# LightShaker-3.net
KiCad netlist of a schematic drawn in EAGLE
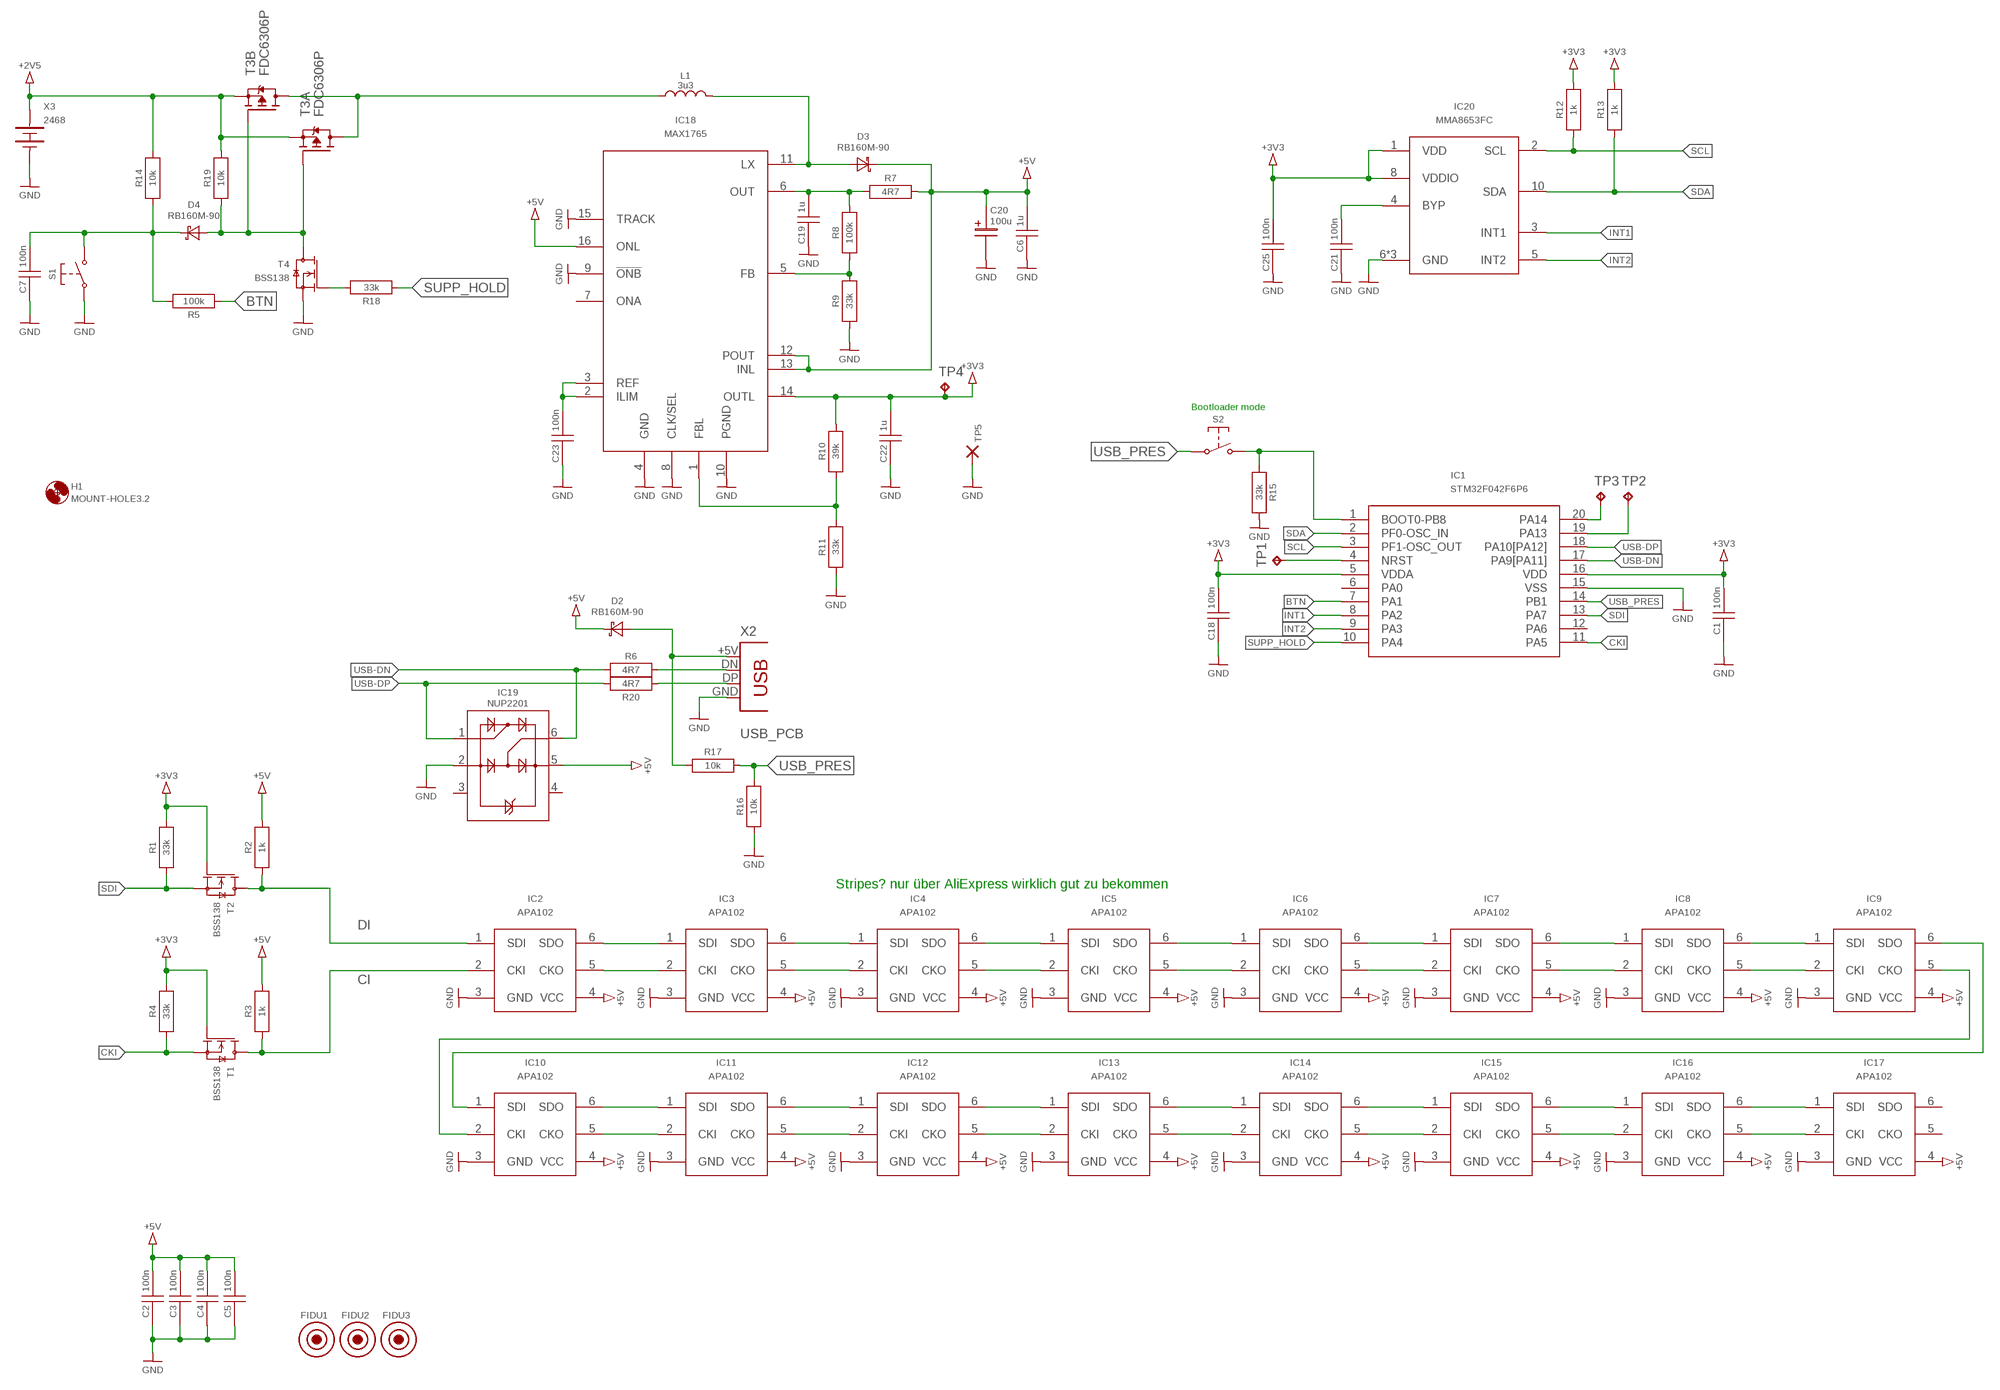
[diagram p0: schematic, sheet 1]

(export (version "E")
  (design (tool "Eeschema 10.0.6"))
  (components
    (comp (ref "C1")
      (value "100n")
      (footprint "eagle-import:SM_1206")
      (fields (field (name "MECHPART") "FALSE") (field (name "PARTNR") "E0001400"))
      (libsource (lib "eagle-import") (part "C1206"))
    )
    (comp (ref "C2")
      (value "100n")
      (footprint "eagle-import:SM_1206")
      (fields (field (name "MECHPART") "FALSE") (field (name "PARTNR") "E0001400"))
      (libsource (lib "eagle-import") (part "C1206"))
    )
    (comp (ref "C3")
      (value "100n")
      (footprint "eagle-import:SM_1206")
      (fields (field (name "MECHPART") "FALSE") (field (name "PARTNR") "E0001400"))
      (libsource (lib "eagle-import") (part "C1206"))
    )
    (comp (ref "C4")
      (value "100n")
      (footprint "eagle-import:SM_1206")
      (fields (field (name "MECHPART") "FALSE") (field (name "PARTNR") "E0001400"))
      (libsource (lib "eagle-import") (part "C1206"))
    )
    (comp (ref "C5")
      (value "100n")
      (footprint "eagle-import:SM_1206")
      (fields (field (name "MECHPART") "FALSE") (field (name "PARTNR") "E0001400"))
      (libsource (lib "eagle-import") (part "C1206"))
    )
    (comp (ref "C6")
      (value "1u")
      (footprint "eagle-import:SM_1206")
      (fields (field (name "MECHPART") "FALSE") (field (name "PARTNR") "E0487200"))
      (libsource (lib "eagle-import") (part "C1206"))
    )
    (comp (ref "C7")
      (value "100n")
      (footprint "eagle-import:SM_1206")
      (fields (field (name "MECHPART") "FALSE") (field (name "PARTNR") "E0001400"))
      (libsource (lib "eagle-import") (part "C1206"))
    )
    (comp (ref "C18")
      (value "100n")
      (footprint "eagle-import:SM_1206")
      (fields (field (name "MECHPART") "FALSE") (field (name "PARTNR") "E0001400"))
      (libsource (lib "eagle-import") (part "C1206"))
    )
    (comp (ref "C19")
      (value "1u")
      (footprint "eagle-import:SM_1206")
      (fields (field (name "MECHPART") "FALSE") (field (name "PARTNR") "E0487200"))
      (libsource (lib "eagle-import") (part "C1206"))
    )
    (comp (ref "C20")
      (value "100u")
      (footprint "eagle-import:SM_SIZE-D")
      (fields (field (name "MECHPART") "FALSE") (field (name "PARTNR") "E0242200"))
      (libsource (lib "eagle-import") (part "CPOLSIZE-D"))
    )
    (comp (ref "C21")
      (value "100n")
      (footprint "eagle-import:SM_1206")
      (fields (field (name "MECHPART") "FALSE") (field (name "PARTNR") "E0001400"))
      (libsource (lib "eagle-import") (part "C1206"))
    )
    (comp (ref "C22")
      (value "1u")
      (footprint "eagle-import:SM_1206")
      (fields (field (name "MECHPART") "FALSE") (field (name "PARTNR") "E0487200"))
      (libsource (lib "eagle-import") (part "C1206"))
    )
    (comp (ref "C23")
      (value "100n")
      (footprint "eagle-import:SM_1206")
      (fields (field (name "MECHPART") "FALSE") (field (name "PARTNR") "E0001400"))
      (libsource (lib "eagle-import") (part "C1206"))
    )
    (comp (ref "C25")
      (value "100n")
      (footprint "eagle-import:SM_1206")
      (fields (field (name "MECHPART") "FALSE") (field (name "PARTNR") "E0001400"))
      (libsource (lib "eagle-import") (part "C1206"))
    )
    (comp (ref "D2")
      (value "RB160M-90")
      (footprint "eagle-import:SM_SOD123_POL")
      (libsource (lib "eagle-import") (part "RB160M-90"))
    )
    (comp (ref "D3")
      (value "RB160M-90")
      (footprint "eagle-import:SM_SOD123_POL")
      (libsource (lib "eagle-import") (part "RB160M-90"))
    )
    (comp (ref "D4")
      (value "RB160M-90")
      (footprint "eagle-import:SM_SOD123_POL")
      (libsource (lib "eagle-import") (part "RB160M-90"))
    )
    (comp (ref "FIDU1")
      (value "FIDU_ROUND_NEW")
      (footprint "eagle-import:FIDUCIAL_LOETSTOPP")
      (libsource (lib "eagle-import") (part "FIDU_ROUND_NEW"))
    )
    (comp (ref "FIDU2")
      (value "FIDU_ROUND_NEW")
      (footprint "eagle-import:FIDUCIAL_LOETSTOPP")
      (libsource (lib "eagle-import") (part "FIDU_ROUND_NEW"))
    )
    (comp (ref "FIDU3")
      (value "FIDU_ROUND_NEW")
      (footprint "eagle-import:FIDUCIAL_LOETSTOPP")
      (libsource (lib "eagle-import") (part "FIDU_ROUND_NEW"))
    )
    (comp (ref "H1")
      (value "MOUNT-HOLE3.2")
      (footprint "eagle-import:3.2")
      (libsource (lib "eagle-import") (part "MOUNT-HOLE3.2"))
    )
    (comp (ref "IC1")
      (value "STM32F042F6P6")
      (footprint "eagle-import:SM_TSSOP20")
      (libsource (lib "eagle-import") (part "STM32F042F6P6"))
    )
    (comp (ref "IC2")
      (value "APA102")
      (footprint "eagle-import:SM_LED_PLCC6")
      (libsource (lib "eagle-import") (part "APA102"))
    )
    (comp (ref "IC3")
      (value "APA102")
      (footprint "eagle-import:SM_LED_PLCC6")
      (libsource (lib "eagle-import") (part "APA102"))
    )
    (comp (ref "IC4")
      (value "APA102")
      (footprint "eagle-import:SM_LED_PLCC6")
      (libsource (lib "eagle-import") (part "APA102"))
    )
    (comp (ref "IC5")
      (value "APA102")
      (footprint "eagle-import:SM_LED_PLCC6")
      (libsource (lib "eagle-import") (part "APA102"))
    )
    (comp (ref "IC6")
      (value "APA102")
      (footprint "eagle-import:SM_LED_PLCC6")
      (libsource (lib "eagle-import") (part "APA102"))
    )
    (comp (ref "IC7")
      (value "APA102")
      (footprint "eagle-import:SM_LED_PLCC6")
      (libsource (lib "eagle-import") (part "APA102"))
    )
    (comp (ref "IC8")
      (value "APA102")
      (footprint "eagle-import:SM_LED_PLCC6")
      (libsource (lib "eagle-import") (part "APA102"))
    )
    (comp (ref "IC9")
      (value "APA102")
      (footprint "eagle-import:SM_LED_PLCC6")
      (libsource (lib "eagle-import") (part "APA102"))
    )
    (comp (ref "IC10")
      (value "APA102")
      (footprint "eagle-import:SM_LED_PLCC6")
      (libsource (lib "eagle-import") (part "APA102"))
    )
    (comp (ref "IC11")
      (value "APA102")
      (footprint "eagle-import:SM_LED_PLCC6")
      (libsource (lib "eagle-import") (part "APA102"))
    )
    (comp (ref "IC12")
      (value "APA102")
      (footprint "eagle-import:SM_LED_PLCC6")
      (libsource (lib "eagle-import") (part "APA102"))
    )
    (comp (ref "IC13")
      (value "APA102")
      (footprint "eagle-import:SM_LED_PLCC6")
      (libsource (lib "eagle-import") (part "APA102"))
    )
    (comp (ref "IC14")
      (value "APA102")
      (footprint "eagle-import:SM_LED_PLCC6")
      (libsource (lib "eagle-import") (part "APA102"))
    )
    (comp (ref "IC15")
      (value "APA102")
      (footprint "eagle-import:SM_LED_PLCC6")
      (libsource (lib "eagle-import") (part "APA102"))
    )
    (comp (ref "IC16")
      (value "APA102")
      (footprint "eagle-import:SM_LED_PLCC6")
      (libsource (lib "eagle-import") (part "APA102"))
    )
    (comp (ref "IC17")
      (value "APA102")
      (footprint "eagle-import:SM_LED_PLCC6")
      (libsource (lib "eagle-import") (part "APA102"))
    )
    (comp (ref "IC18")
      (value "MAX1765")
      (footprint "eagle-import:SM_QSOP16")
      (libsource (lib "eagle-import") (part "MAX1765"))
    )
    (comp (ref "IC19")
      (value "NUP2201")
      (footprint "eagle-import:TSOP6")
      (libsource (lib "eagle-import") (part "NUP2201"))
    )
    (comp (ref "IC20")
      (value "MMA8653FC")
      (footprint "eagle-import:SM_DFN10")
      (libsource (lib "eagle-import") (part "MMA8653FC"))
    )
    (comp (ref "L1")
      (value "3u3")
      (footprint "eagle-import:SM_L_MOS6020")
      (libsource (lib "eagle-import") (part "L_MOS6020"))
    )
    (comp (ref "R1")
      (value "33k")
      (footprint "eagle-import:SM_1206")
      (fields (field (name "MECHPART") "FALSE") (field (name "PARTNR") "E0149800"))
      (libsource (lib "eagle-import") (part "R1206"))
    )
    (comp (ref "R2")
      (value "1k")
      (footprint "eagle-import:SM_1206")
      (fields (field (name "MECHPART") "FALSE") (field (name "PARTNR") "E0002500"))
      (libsource (lib "eagle-import") (part "R1206"))
    )
    (comp (ref "R3")
      (value "1k")
      (footprint "eagle-import:SM_1206")
      (fields (field (name "MECHPART") "FALSE") (field (name "PARTNR") "E0002500"))
      (libsource (lib "eagle-import") (part "R1206"))
    )
    (comp (ref "R4")
      (value "33k")
      (footprint "eagle-import:SM_1206")
      (fields (field (name "MECHPART") "FALSE") (field (name "PARTNR") "E0149800"))
      (libsource (lib "eagle-import") (part "R1206"))
    )
    (comp (ref "R5")
      (value "100k")
      (footprint "eagle-import:SM_1206")
      (fields (field (name "MECHPART") "FALSE"))
      (libsource (lib "eagle-import") (part "R1206"))
    )
    (comp (ref "R6")
      (value "4R7")
      (footprint "eagle-import:SM_1206")
      (fields (field (name "MECHPART") "FALSE"))
      (libsource (lib "eagle-import") (part "R1206"))
    )
    (comp (ref "R7")
      (value "4R7")
      (footprint "eagle-import:SM_1206")
      (fields (field (name "MECHPART") "FALSE") (field (name "PARTNR") "E0821300"))
      (libsource (lib "eagle-import") (part "R1206"))
    )
    (comp (ref "R8")
      (value "100k")
      (footprint "eagle-import:SM_1206")
      (fields (field (name "MECHPART") "FALSE") (field (name "PARTNR") "E0002800"))
      (libsource (lib "eagle-import") (part "R1206"))
    )
    (comp (ref "R9")
      (value "33k")
      (footprint "eagle-import:SM_1206")
      (fields (field (name "MECHPART") "FALSE") (field (name "PARTNR") "E0149800"))
      (libsource (lib "eagle-import") (part "R1206"))
    )
    (comp (ref "R10")
      (value "39k")
      (footprint "eagle-import:SM_1206")
      (fields (field (name "MECHPART") "FALSE"))
      (libsource (lib "eagle-import") (part "R1206"))
    )
    (comp (ref "R11")
      (value "33k")
      (footprint "eagle-import:SM_1206")
      (fields (field (name "MECHPART") "FALSE") (field (name "PARTNR") "E0149800"))
      (libsource (lib "eagle-import") (part "R1206"))
    )
    (comp (ref "R12")
      (value "1k")
      (footprint "eagle-import:SM_1206")
      (fields (field (name "MECHPART") "FALSE") (field (name "PARTNR") "E0002500"))
      (libsource (lib "eagle-import") (part "R1206"))
    )
    (comp (ref "R13")
      (value "1k")
      (footprint "eagle-import:SM_1206")
      (fields (field (name "MECHPART") "FALSE") (field (name "PARTNR") "E0002500"))
      (libsource (lib "eagle-import") (part "R1206"))
    )
    (comp (ref "R14")
      (value "10k")
      (footprint "eagle-import:SM_1206")
      (fields (field (name "MECHPART") "FALSE") (field (name "PARTNR") "E0002700"))
      (libsource (lib "eagle-import") (part "R1206"))
    )
    (comp (ref "R15")
      (value "33k")
      (footprint "eagle-import:SM_1206")
      (fields (field (name "MECHPART") "FALSE") (field (name "PARTNR") "E0149800"))
      (libsource (lib "eagle-import") (part "R1206"))
    )
    (comp (ref "R16")
      (value "10k")
      (footprint "eagle-import:SM_1206")
      (fields (field (name "MECHPART") "FALSE") (field (name "PARTNR") "E0002700"))
      (libsource (lib "eagle-import") (part "R1206"))
    )
    (comp (ref "R17")
      (value "10k")
      (footprint "eagle-import:SM_1206")
      (fields (field (name "MECHPART") "FALSE") (field (name "PARTNR") "E0002700"))
      (libsource (lib "eagle-import") (part "R1206"))
    )
    (comp (ref "R18")
      (value "33k")
      (footprint "eagle-import:SM_1206")
      (fields (field (name "MECHPART") "FALSE") (field (name "PARTNR") "E0149800"))
      (libsource (lib "eagle-import") (part "R1206"))
    )
    (comp (ref "R19")
      (value "10k")
      (footprint "eagle-import:SM_1206")
      (fields (field (name "MECHPART") "FALSE") (field (name "PARTNR") "E0002800"))
      (libsource (lib "eagle-import") (part "R1206"))
    )
    (comp (ref "R20")
      (value "4R7")
      (footprint "eagle-import:SM_1206")
      (fields (field (name "MECHPART") "FALSE"))
      (libsource (lib "eagle-import") (part "R1206"))
    )
    (comp (ref "S1")
      (value "PUSH-BUTTON_SMD")
      (footprint "eagle-import:PUSH-BUTTON_SMD")
      (libsource (lib "eagle-import") (part "PUSH-BUTTON_SMD"))
    )
    (comp (ref "S2")
      (value "PUSH-BUTTON_SMD")
      (footprint "eagle-import:PUSH-BUTTON_SMD")
      (libsource (lib "eagle-import") (part "PUSH-BUTTON_SMD"))
    )
    (comp (ref "T1")
      (value "BSS138")
      (footprint "eagle-import:SM_SOT23")
      (libsource (lib "eagle-import") (part "BSS138"))
    )
    (comp (ref "T2")
      (value "BSS138")
      (footprint "eagle-import:SM_SOT23")
      (libsource (lib "eagle-import") (part "BSS138"))
    )
    (comp (ref "T3")
      (value "FDC6306P")
      (footprint "eagle-import:TSOP6")
      (fields (field (name "PARTNR") "E0662100"))
      (libsource (lib "eagle-import") (part "FDC6306P"))
    )
    (comp (ref "T4")
      (value "BSS138")
      (footprint "eagle-import:SM_SOT23")
      (libsource (lib "eagle-import") (part "BSS138"))
    )
    (comp (ref "TP1")
      (value "TPTP12R")
      (footprint "eagle-import:TP12R")
      (libsource (lib "eagle-import") (part "TPTP12R"))
    )
    (comp (ref "TP2")
      (value "TPTP12R")
      (footprint "eagle-import:TP12R")
      (libsource (lib "eagle-import") (part "TPTP12R"))
    )
    (comp (ref "TP3")
      (value "TPTP12R")
      (footprint "eagle-import:TP12R")
      (libsource (lib "eagle-import") (part "TPTP12R"))
    )
    (comp (ref "TP4")
      (value "TPTP12R")
      (footprint "eagle-import:TP12R")
      (libsource (lib "eagle-import") (part "TPTP12R"))
    )
    (comp (ref "TP5")
      (value "CHECKER_1206")
      (footprint "eagle-import:SM_RCW_1206")
      (libsource (lib "eagle-import") (part "CHECKER_1206"))
    )
    (comp (ref "X2")
      (value "USB_PCB")
      (footprint "eagle-import:USB_PCB")
      (libsource (lib "eagle-import") (part "USB_PCB"))
    )
    (comp (ref "X3")
      (value "2468")
      (footprint "eagle-import:2468")
      (libsource (lib "eagle-import") (part "2468"))
    )
  )
  (nets
    (net (code "1") (name "+2V5") (class "Default")
      (node (ref "R14") (pin "2") (pinfunction "2_2") (pintype "bidirectional"))
      (node (ref "R19") (pin "2") (pinfunction "2_2") (pintype "bidirectional"))
      (node (ref "T3") (pin "2") (pinfunction "S_2") (pintype "passive"))
      (node (ref "T3") (pin "5") (pinfunction "S_5") (pintype "passive"))
      (node (ref "X3") (pin "POS") (pinfunction "POS_POS") (pintype "bidirectional"))
    )
    (net (code "2") (name "+3V3") (class "Default")
      (node (ref "C1") (pin "2") (pinfunction "2_2") (pintype "bidirectional"))
      (node (ref "C18") (pin "2") (pinfunction "2_2") (pintype "bidirectional"))
      (node (ref "C22") (pin "2") (pinfunction "2_2") (pintype "bidirectional"))
      (node (ref "C25") (pin "2") (pinfunction "2_2") (pintype "bidirectional"))
      (node (ref "IC1") (pin "16") (pinfunction "VDD_16") (pintype "bidirectional"))
      (node (ref "IC1") (pin "5") (pinfunction "VDDA_5") (pintype "bidirectional"))
      (node (ref "IC18") (pin "14") (pinfunction "OUTL_14") (pintype "bidirectional"))
      (node (ref "IC20") (pin "1") (pinfunction "VDD_1") (pintype "bidirectional"))
      (node (ref "IC20") (pin "8") (pinfunction "VDDIO_8") (pintype "bidirectional"))
      (node (ref "R1") (pin "2") (pinfunction "2_2") (pintype "bidirectional"))
      (node (ref "R10") (pin "2") (pinfunction "2_2") (pintype "bidirectional"))
      (node (ref "R12") (pin "2") (pinfunction "2_2") (pintype "bidirectional"))
      (node (ref "R13") (pin "2") (pinfunction "2_2") (pintype "bidirectional"))
      (node (ref "R4") (pin "2") (pinfunction "2_2") (pintype "bidirectional"))
      (node (ref "T1") (pin "1") (pinfunction "G_1") (pintype "bidirectional"))
      (node (ref "T2") (pin "1") (pinfunction "G_1") (pintype "bidirectional"))
      (node (ref "TP4") (pin "TP") (pinfunction "TP_TP") (pintype "input"))
    )
    (net (code "3") (name "+5V") (class "Default")
      (node (ref "C2") (pin "2") (pinfunction "2_2") (pintype "bidirectional"))
      (node (ref "C20") (pin "POS") (pinfunction "POS_POS") (pintype "bidirectional"))
      (node (ref "C3") (pin "2") (pinfunction "2_2") (pintype "bidirectional"))
      (node (ref "C4") (pin "2") (pinfunction "2_2") (pintype "bidirectional"))
      (node (ref "C5") (pin "2") (pinfunction "2_2") (pintype "bidirectional"))
      (node (ref "C6") (pin "2") (pinfunction "2_2") (pintype "bidirectional"))
      (node (ref "D2") (pin "C") (pinfunction "C_C") (pintype "bidirectional"))
      (node (ref "D3") (pin "C") (pinfunction "C_C") (pintype "bidirectional"))
      (node (ref "IC10") (pin "4") (pinfunction "VCC_4") (pintype "bidirectional"))
      (node (ref "IC11") (pin "4") (pinfunction "VCC_4") (pintype "bidirectional"))
      (node (ref "IC12") (pin "4") (pinfunction "VCC_4") (pintype "bidirectional"))
      (node (ref "IC13") (pin "4") (pinfunction "VCC_4") (pintype "bidirectional"))
      (node (ref "IC14") (pin "4") (pinfunction "VCC_4") (pintype "bidirectional"))
      (node (ref "IC15") (pin "4") (pinfunction "VCC_4") (pintype "bidirectional"))
      (node (ref "IC16") (pin "4") (pinfunction "VCC_4") (pintype "bidirectional"))
      (node (ref "IC17") (pin "4") (pinfunction "VCC_4") (pintype "bidirectional"))
      (node (ref "IC18") (pin "12") (pinfunction "POUT_12") (pintype "bidirectional"))
      (node (ref "IC18") (pin "13") (pinfunction "INL_13") (pintype "bidirectional"))
      (node (ref "IC18") (pin "16") (pinfunction "ONL_16") (pintype "bidirectional"))
      (node (ref "IC19") (pin "5") (pinfunction "VP_5") (pintype "bidirectional"))
      (node (ref "IC2") (pin "4") (pinfunction "VCC_4") (pintype "bidirectional"))
      (node (ref "IC3") (pin "4") (pinfunction "VCC_4") (pintype "bidirectional"))
      (node (ref "IC4") (pin "4") (pinfunction "VCC_4") (pintype "bidirectional"))
      (node (ref "IC5") (pin "4") (pinfunction "VCC_4") (pintype "bidirectional"))
      (node (ref "IC6") (pin "4") (pinfunction "VCC_4") (pintype "bidirectional"))
      (node (ref "IC7") (pin "4") (pinfunction "VCC_4") (pintype "bidirectional"))
      (node (ref "IC8") (pin "4") (pinfunction "VCC_4") (pintype "bidirectional"))
      (node (ref "IC9") (pin "4") (pinfunction "VCC_4") (pintype "bidirectional"))
      (node (ref "R2") (pin "2") (pinfunction "2_2") (pintype "bidirectional"))
      (node (ref "R3") (pin "2") (pinfunction "2_2") (pintype "bidirectional"))
      (node (ref "R7") (pin "2") (pinfunction "2_2") (pintype "bidirectional"))
    )
    (net (code "4") (name "/CI") (class "Default")
      (node (ref "IC2") (pin "2") (pinfunction "CKI_2") (pintype "bidirectional"))
      (node (ref "R3") (pin "1") (pinfunction "1_1") (pintype "bidirectional"))
      (node (ref "T1") (pin "3") (pinfunction "D_3") (pintype "bidirectional"))
    )
    (net (code "5") (name "/DI") (class "Default")
      (node (ref "IC2") (pin "1") (pinfunction "SDI_1") (pintype "bidirectional"))
      (node (ref "R2") (pin "1") (pinfunction "1_1") (pintype "bidirectional"))
      (node (ref "T2") (pin "3") (pinfunction "D_3") (pintype "bidirectional"))
    )
    (net (code "6") (name "BTN") (class "Default")
      (node (ref "IC1") (pin "7") (pinfunction "PA1_7") (pintype "bidirectional"))
      (node (ref "R5") (pin "1") (pinfunction "1_1") (pintype "bidirectional"))
    )
    (net (code "7") (name "CKI") (class "Default")
      (node (ref "IC1") (pin "11") (pinfunction "PA5_11") (pintype "bidirectional"))
      (node (ref "R4") (pin "1") (pinfunction "1_1") (pintype "bidirectional"))
      (node (ref "T1") (pin "2") (pinfunction "S_2") (pintype "bidirectional"))
    )
    (net (code "8") (name "GND") (class "Default")
      (node (ref "C1") (pin "1") (pinfunction "1_1") (pintype "bidirectional"))
      (node (ref "C18") (pin "1") (pinfunction "1_1") (pintype "bidirectional"))
      (node (ref "C19") (pin "1") (pinfunction "1_1") (pintype "bidirectional"))
      (node (ref "C2") (pin "1") (pinfunction "1_1") (pintype "bidirectional"))
      (node (ref "C20") (pin "NEG") (pinfunction "NEG_NEG") (pintype "bidirectional"))
      (node (ref "C21") (pin "1") (pinfunction "1_1") (pintype "bidirectional"))
      (node (ref "C22") (pin "1") (pinfunction "1_1") (pintype "bidirectional"))
      (node (ref "C23") (pin "1") (pinfunction "1_1") (pintype "bidirectional"))
      (node (ref "C25") (pin "1") (pinfunction "1_1") (pintype "bidirectional"))
      (node (ref "C3") (pin "1") (pinfunction "1_1") (pintype "bidirectional"))
      (node (ref "C4") (pin "1") (pinfunction "1_1") (pintype "bidirectional"))
      (node (ref "C5") (pin "1") (pinfunction "1_1") (pintype "bidirectional"))
      (node (ref "C6") (pin "1") (pinfunction "1_1") (pintype "bidirectional"))
      (node (ref "C7") (pin "1") (pinfunction "1_1") (pintype "bidirectional"))
      (node (ref "IC1") (pin "15") (pinfunction "VSS_15") (pintype "bidirectional"))
      (node (ref "IC10") (pin "3") (pinfunction "GND_3") (pintype "bidirectional"))
      (node (ref "IC11") (pin "3") (pinfunction "GND_3") (pintype "bidirectional"))
      (node (ref "IC12") (pin "3") (pinfunction "GND_3") (pintype "bidirectional"))
      (node (ref "IC13") (pin "3") (pinfunction "GND_3") (pintype "bidirectional"))
      (node (ref "IC14") (pin "3") (pinfunction "GND_3") (pintype "bidirectional"))
      (node (ref "IC15") (pin "3") (pinfunction "GND_3") (pintype "bidirectional"))
      (node (ref "IC16") (pin "3") (pinfunction "GND_3") (pintype "bidirectional"))
      (node (ref "IC17") (pin "3") (pinfunction "GND_3") (pintype "bidirectional"))
      (node (ref "IC18") (pin "10") (pinfunction "PGND_10") (pintype "bidirectional"))
      (node (ref "IC18") (pin "15") (pinfunction "TRACK_15") (pintype "bidirectional"))
      (node (ref "IC18") (pin "4") (pinfunction "GND_4") (pintype "bidirectional"))
      (node (ref "IC18") (pin "8") (pinfunction "CLK/SEL_8") (pintype "bidirectional"))
      (node (ref "IC18") (pin "9") (pinfunction "~{ONB}_9") (pintype "bidirectional"))
      (node (ref "IC19") (pin "2") (pinfunction "GND_2") (pintype "bidirectional"))
      (node (ref "IC2") (pin "3") (pinfunction "GND_3") (pintype "bidirectional"))
      (node (ref "IC20") (pin "6") (pinfunction "GND_6") (pintype "bidirectional"))
      (node (ref "IC20") (pin "7") (pinfunction "GND_7") (pintype "bidirectional"))
      (node (ref "IC20") (pin "9") (pinfunction "GND_9") (pintype "bidirectional"))
      (node (ref "IC3") (pin "3") (pinfunction "GND_3") (pintype "bidirectional"))
      (node (ref "IC4") (pin "3") (pinfunction "GND_3") (pintype "bidirectional"))
      (node (ref "IC5") (pin "3") (pinfunction "GND_3") (pintype "bidirectional"))
      (node (ref "IC6") (pin "3") (pinfunction "GND_3") (pintype "bidirectional"))
      (node (ref "IC7") (pin "3") (pinfunction "GND_3") (pintype "bidirectional"))
      (node (ref "IC8") (pin "3") (pinfunction "GND_3") (pintype "bidirectional"))
      (node (ref "IC9") (pin "3") (pinfunction "GND_3") (pintype "bidirectional"))
      (node (ref "R11") (pin "1") (pinfunction "1_1") (pintype "bidirectional"))
      (node (ref "R15") (pin "2") (pinfunction "2_2") (pintype "bidirectional"))
      (node (ref "R16") (pin "1") (pinfunction "1_1") (pintype "bidirectional"))
      (node (ref "R9") (pin "1") (pinfunction "1_1") (pintype "bidirectional"))
      (node (ref "S1") (pin "1") (pinfunction "P_1") (pintype "passive"))
      (node (ref "S1") (pin "2") (pinfunction "P_2") (pintype "passive"))
      (node (ref "T4") (pin "2") (pinfunction "S_2") (pintype "bidirectional"))
      (node (ref "TP5") (pin "1") (pinfunction "P_1") (pintype "passive"))
      (node (ref "X2") (pin "GND") (pinfunction "GND_GND") (pintype "passive"))
      (node (ref "X3") (pin "NEG") (pinfunction "NEG_NEG") (pintype "bidirectional"))
    )
    (net (code "9") (name "INT1") (class "Default")
      (node (ref "IC1") (pin "8") (pinfunction "PA2_8") (pintype "bidirectional"))
      (node (ref "IC20") (pin "3") (pinfunction "INT1_3") (pintype "bidirectional"))
    )
    (net (code "10") (name "INT2") (class "Default")
      (node (ref "IC1") (pin "9") (pinfunction "PA3_9") (pintype "bidirectional"))
      (node (ref "IC20") (pin "5") (pinfunction "INT2_5") (pintype "bidirectional"))
    )
    (net (code "11") (name "Net-(C7-Pad2)") (class "Default")
      (node (ref "C7") (pin "2") (pinfunction "2_2") (pintype "bidirectional"))
      (node (ref "D4") (pin "C") (pinfunction "C_C") (pintype "bidirectional"))
      (node (ref "R14") (pin "1") (pinfunction "1_1") (pintype "bidirectional"))
      (node (ref "R5") (pin "2") (pinfunction "2_2") (pintype "bidirectional"))
      (node (ref "S1") (pin "3") (pinfunction "S_3") (pintype "passive"))
      (node (ref "S1") (pin "4") (pinfunction "S_4") (pintype "passive"))
    )
    (net (code "12") (name "Net-(D2-PadA)") (class "Default")
      (node (ref "D2") (pin "A") (pinfunction "A_A") (pintype "bidirectional"))
      (node (ref "R17") (pin "1") (pinfunction "1_1") (pintype "bidirectional"))
      (node (ref "X2") (pin "+5V") (pinfunction "+5V_+5V") (pintype "passive"))
    )
    (net (code "13") (name "Net-(IC1-BOOT0-PB8)") (class "Default")
      (node (ref "IC1") (pin "1") (pinfunction "BOOT0-PB8_1") (pintype "bidirectional"))
      (node (ref "R15") (pin "1") (pinfunction "1_1") (pintype "bidirectional"))
      (node (ref "S2") (pin "3") (pinfunction "S_3") (pintype "passive"))
      (node (ref "S2") (pin "4") (pinfunction "S_4") (pintype "passive"))
    )
    (net (code "14") (name "Net-(IC1-NRST)") (class "Default")
      (node (ref "IC1") (pin "4") (pinfunction "NRST_4") (pintype "bidirectional"))
      (node (ref "TP1") (pin "TP") (pinfunction "TP_TP") (pintype "input"))
    )
    (net (code "15") (name "Net-(IC1-PA13)") (class "Default")
      (node (ref "IC1") (pin "19") (pinfunction "PA13_19") (pintype "bidirectional"))
      (node (ref "TP2") (pin "TP") (pinfunction "TP_TP") (pintype "input"))
    )
    (net (code "16") (name "Net-(IC1-PA14)") (class "Default")
      (node (ref "IC1") (pin "20") (pinfunction "PA14_20") (pintype "bidirectional"))
      (node (ref "TP3") (pin "TP") (pinfunction "TP_TP") (pintype "input"))
    )
    (net (code "17") (name "Net-(IC2-CKO)") (class "Default")
      (node (ref "IC2") (pin "5") (pinfunction "CKO_5") (pintype "bidirectional"))
      (node (ref "IC3") (pin "2") (pinfunction "CKI_2") (pintype "bidirectional"))
    )
    (net (code "18") (name "Net-(IC2-SDO)") (class "Default")
      (node (ref "IC2") (pin "6") (pinfunction "SDO_6") (pintype "bidirectional"))
      (node (ref "IC3") (pin "1") (pinfunction "SDI_1") (pintype "bidirectional"))
    )
    (net (code "19") (name "Net-(IC3-CKO)") (class "Default")
      (node (ref "IC3") (pin "5") (pinfunction "CKO_5") (pintype "bidirectional"))
      (node (ref "IC4") (pin "2") (pinfunction "CKI_2") (pintype "bidirectional"))
    )
    (net (code "20") (name "Net-(IC3-SDO)") (class "Default")
      (node (ref "IC3") (pin "6") (pinfunction "SDO_6") (pintype "bidirectional"))
      (node (ref "IC4") (pin "1") (pinfunction "SDI_1") (pintype "bidirectional"))
    )
    (net (code "21") (name "Net-(IC4-CKO)") (class "Default")
      (node (ref "IC4") (pin "5") (pinfunction "CKO_5") (pintype "bidirectional"))
      (node (ref "IC5") (pin "2") (pinfunction "CKI_2") (pintype "bidirectional"))
    )
    (net (code "22") (name "Net-(IC4-SDO)") (class "Default")
      (node (ref "IC4") (pin "6") (pinfunction "SDO_6") (pintype "bidirectional"))
      (node (ref "IC5") (pin "1") (pinfunction "SDI_1") (pintype "bidirectional"))
    )
    (net (code "23") (name "Net-(IC5-CKO)") (class "Default")
      (node (ref "IC5") (pin "5") (pinfunction "CKO_5") (pintype "bidirectional"))
      (node (ref "IC6") (pin "2") (pinfunction "CKI_2") (pintype "bidirectional"))
    )
    (net (code "24") (name "Net-(IC5-SDO)") (class "Default")
      (node (ref "IC5") (pin "6") (pinfunction "SDO_6") (pintype "bidirectional"))
      (node (ref "IC6") (pin "1") (pinfunction "SDI_1") (pintype "bidirectional"))
    )
    (net (code "25") (name "Net-(IC6-CKO)") (class "Default")
      (node (ref "IC6") (pin "5") (pinfunction "CKO_5") (pintype "bidirectional"))
      (node (ref "IC7") (pin "2") (pinfunction "CKI_2") (pintype "bidirectional"))
    )
    (net (code "26") (name "Net-(IC6-SDO)") (class "Default")
      (node (ref "IC6") (pin "6") (pinfunction "SDO_6") (pintype "bidirectional"))
      (node (ref "IC7") (pin "1") (pinfunction "SDI_1") (pintype "bidirectional"))
    )
    (net (code "27") (name "Net-(IC7-CKO)") (class "Default")
      (node (ref "IC7") (pin "5") (pinfunction "CKO_5") (pintype "bidirectional"))
      (node (ref "IC8") (pin "2") (pinfunction "CKI_2") (pintype "bidirectional"))
    )
    (net (code "28") (name "Net-(IC7-SDO)") (class "Default")
      (node (ref "IC7") (pin "6") (pinfunction "SDO_6") (pintype "bidirectional"))
      (node (ref "IC8") (pin "1") (pinfunction "SDI_1") (pintype "bidirectional"))
    )
    (net (code "29") (name "Net-(IC8-CKO)") (class "Default")
      (node (ref "IC8") (pin "5") (pinfunction "CKO_5") (pintype "bidirectional"))
      (node (ref "IC9") (pin "2") (pinfunction "CKI_2") (pintype "bidirectional"))
    )
    (net (code "30") (name "Net-(IC8-SDO)") (class "Default")
      (node (ref "IC8") (pin "6") (pinfunction "SDO_6") (pintype "bidirectional"))
      (node (ref "IC9") (pin "1") (pinfunction "SDI_1") (pintype "bidirectional"))
    )
    (net (code "31") (name "Net-(IC10-CKI)") (class "Default")
      (node (ref "IC10") (pin "2") (pinfunction "CKI_2") (pintype "bidirectional"))
      (node (ref "IC9") (pin "5") (pinfunction "CKO_5") (pintype "bidirectional"))
    )
    (net (code "32") (name "Net-(IC10-CKO)") (class "Default")
      (node (ref "IC10") (pin "5") (pinfunction "CKO_5") (pintype "bidirectional"))
      (node (ref "IC11") (pin "2") (pinfunction "CKI_2") (pintype "bidirectional"))
    )
    (net (code "33") (name "Net-(IC10-SDI)") (class "Default")
      (node (ref "IC10") (pin "1") (pinfunction "SDI_1") (pintype "bidirectional"))
      (node (ref "IC9") (pin "6") (pinfunction "SDO_6") (pintype "bidirectional"))
    )
    (net (code "34") (name "Net-(IC10-SDO)") (class "Default")
      (node (ref "IC10") (pin "6") (pinfunction "SDO_6") (pintype "bidirectional"))
      (node (ref "IC11") (pin "1") (pinfunction "SDI_1") (pintype "bidirectional"))
    )
    (net (code "35") (name "Net-(IC11-CKO)") (class "Default")
      (node (ref "IC11") (pin "5") (pinfunction "CKO_5") (pintype "bidirectional"))
      (node (ref "IC12") (pin "2") (pinfunction "CKI_2") (pintype "bidirectional"))
    )
    (net (code "36") (name "Net-(IC11-SDO)") (class "Default")
      (node (ref "IC11") (pin "6") (pinfunction "SDO_6") (pintype "bidirectional"))
      (node (ref "IC12") (pin "1") (pinfunction "SDI_1") (pintype "bidirectional"))
    )
    (net (code "37") (name "Net-(IC12-CKO)") (class "Default")
      (node (ref "IC12") (pin "5") (pinfunction "CKO_5") (pintype "bidirectional"))
      (node (ref "IC13") (pin "2") (pinfunction "CKI_2") (pintype "bidirectional"))
    )
    (net (code "38") (name "Net-(IC12-SDO)") (class "Default")
      (node (ref "IC12") (pin "6") (pinfunction "SDO_6") (pintype "bidirectional"))
      (node (ref "IC13") (pin "1") (pinfunction "SDI_1") (pintype "bidirectional"))
    )
    (net (code "39") (name "Net-(IC13-CKO)") (class "Default")
      (node (ref "IC13") (pin "5") (pinfunction "CKO_5") (pintype "bidirectional"))
      (node (ref "IC14") (pin "2") (pinfunction "CKI_2") (pintype "bidirectional"))
    )
    (net (code "40") (name "Net-(IC13-SDO)") (class "Default")
      (node (ref "IC13") (pin "6") (pinfunction "SDO_6") (pintype "bidirectional"))
      (node (ref "IC14") (pin "1") (pinfunction "SDI_1") (pintype "bidirectional"))
    )
    (net (code "41") (name "Net-(IC14-CKO)") (class "Default")
      (node (ref "IC14") (pin "5") (pinfunction "CKO_5") (pintype "bidirectional"))
      (node (ref "IC15") (pin "2") (pinfunction "CKI_2") (pintype "bidirectional"))
    )
    (net (code "42") (name "Net-(IC14-SDO)") (class "Default")
      (node (ref "IC14") (pin "6") (pinfunction "SDO_6") (pintype "bidirectional"))
      (node (ref "IC15") (pin "1") (pinfunction "SDI_1") (pintype "bidirectional"))
    )
    (net (code "43") (name "Net-(IC15-CKO)") (class "Default")
      (node (ref "IC15") (pin "5") (pinfunction "CKO_5") (pintype "bidirectional"))
      (node (ref "IC16") (pin "2") (pinfunction "CKI_2") (pintype "bidirectional"))
    )
    (net (code "44") (name "Net-(IC15-SDO)") (class "Default")
      (node (ref "IC15") (pin "6") (pinfunction "SDO_6") (pintype "bidirectional"))
      (node (ref "IC16") (pin "1") (pinfunction "SDI_1") (pintype "bidirectional"))
    )
    (net (code "45") (name "Net-(IC16-CKO)") (class "Default")
      (node (ref "IC16") (pin "5") (pinfunction "CKO_5") (pintype "bidirectional"))
      (node (ref "IC17") (pin "2") (pinfunction "CKI_2") (pintype "bidirectional"))
    )
    (net (code "46") (name "Net-(IC16-SDO)") (class "Default")
      (node (ref "IC16") (pin "6") (pinfunction "SDO_6") (pintype "bidirectional"))
      (node (ref "IC17") (pin "1") (pinfunction "SDI_1") (pintype "bidirectional"))
    )
    (net (code "47") (name "Net-(IC18-FB)") (class "Default")
      (node (ref "IC18") (pin "5") (pinfunction "FB_5") (pintype "bidirectional"))
      (node (ref "R8") (pin "1") (pinfunction "1_1") (pintype "bidirectional"))
      (node (ref "R9") (pin "2") (pinfunction "2_2") (pintype "bidirectional"))
    )
    (net (code "48") (name "Net-(IC18-FBL)") (class "Default")
      (node (ref "IC18") (pin "1") (pinfunction "FBL_1") (pintype "bidirectional"))
      (node (ref "R10") (pin "1") (pinfunction "1_1") (pintype "bidirectional"))
      (node (ref "R11") (pin "2") (pinfunction "2_2") (pintype "bidirectional"))
    )
    (net (code "49") (name "Net-(IC18-ILIM)") (class "Default")
      (node (ref "C23") (pin "2") (pinfunction "2_2") (pintype "bidirectional"))
      (node (ref "IC18") (pin "2") (pinfunction "ILIM_2") (pintype "bidirectional"))
      (node (ref "IC18") (pin "3") (pinfunction "REF_3") (pintype "bidirectional"))
    )
    (net (code "50") (name "Net-(IC18-LX)") (class "Default")
      (node (ref "D3") (pin "A") (pinfunction "A_A") (pintype "bidirectional"))
      (node (ref "IC18") (pin "11") (pinfunction "LX_11") (pintype "bidirectional"))
      (node (ref "L1") (pin "2") (pinfunction "2_2") (pintype "bidirectional"))
    )
    (net (code "51") (name "Net-(IC18-OUT)") (class "Default")
      (node (ref "C19") (pin "2") (pinfunction "2_2") (pintype "bidirectional"))
      (node (ref "IC18") (pin "6") (pinfunction "OUT_6") (pintype "bidirectional"))
      (node (ref "R7") (pin "1") (pinfunction "1_1") (pintype "bidirectional"))
      (node (ref "R8") (pin "2") (pinfunction "2_2") (pintype "bidirectional"))
    )
    (net (code "52") (name "Net-(IC20-BYP)") (class "Default")
      (node (ref "C21") (pin "2") (pinfunction "2_2") (pintype "bidirectional"))
      (node (ref "IC20") (pin "4") (pinfunction "BYP_4") (pintype "bidirectional"))
    )
    (net (code "53") (name "Net-(R6-Pad2)") (class "Default")
      (node (ref "R6") (pin "2") (pinfunction "2_2") (pintype "bidirectional"))
      (node (ref "X2") (pin "DN") (pinfunction "DN_DN") (pintype "passive"))
    )
    (net (code "54") (name "Net-(R20-Pad1)") (class "Default")
      (node (ref "R20") (pin "1") (pinfunction "1_1") (pintype "bidirectional"))
      (node (ref "X2") (pin "DP") (pinfunction "DP_DP") (pintype "passive"))
    )
    (net (code "55") (name "Net-(T3A-D)") (class "Default")
      (node (ref "L1") (pin "1") (pinfunction "1_1") (pintype "bidirectional"))
      (node (ref "T3") (pin "4") (pinfunction "D_4") (pintype "passive"))
      (node (ref "T3") (pin "6") (pinfunction "D_6") (pintype "passive"))
    )
    (net (code "56") (name "Net-(T3A-G)") (class "Default")
      (node (ref "D4") (pin "A") (pinfunction "A_A") (pintype "bidirectional"))
      (node (ref "R19") (pin "1") (pinfunction "1_1") (pintype "bidirectional"))
      (node (ref "T3") (pin "1") (pinfunction "G_1") (pintype "passive"))
      (node (ref "T3") (pin "3") (pinfunction "G_3") (pintype "passive"))
      (node (ref "T4") (pin "3") (pinfunction "D_3") (pintype "bidirectional"))
    )
    (net (code "57") (name "Net-(T4-G)") (class "Default")
      (node (ref "R18") (pin "2") (pinfunction "2_2") (pintype "bidirectional"))
      (node (ref "T4") (pin "1") (pinfunction "G_1") (pintype "bidirectional"))
    )
    (net (code "58") (name "SCL") (class "Default")
      (node (ref "IC1") (pin "3") (pinfunction "PF1-OSC_OUT_3") (pintype "bidirectional"))
      (node (ref "IC20") (pin "2") (pinfunction "SCL_2") (pintype "bidirectional"))
      (node (ref "R12") (pin "1") (pinfunction "1_1") (pintype "bidirectional"))
    )
    (net (code "59") (name "SDA") (class "Default")
      (node (ref "IC1") (pin "2") (pinfunction "PF0-OSC_IN_2") (pintype "bidirectional"))
      (node (ref "IC20") (pin "10") (pinfunction "SDA_10") (pintype "bidirectional"))
      (node (ref "R13") (pin "1") (pinfunction "1_1") (pintype "bidirectional"))
    )
    (net (code "60") (name "SDI") (class "Default")
      (node (ref "IC1") (pin "13") (pinfunction "PA7_13") (pintype "bidirectional"))
      (node (ref "R1") (pin "1") (pinfunction "1_1") (pintype "bidirectional"))
      (node (ref "T2") (pin "2") (pinfunction "S_2") (pintype "bidirectional"))
    )
    (net (code "61") (name "SUPP_HOLD") (class "Default")
      (node (ref "IC1") (pin "10") (pinfunction "PA4_10") (pintype "bidirectional"))
      (node (ref "R18") (pin "1") (pinfunction "1_1") (pintype "bidirectional"))
    )
    (net (code "62") (name "USB-DN") (class "Default")
      (node (ref "IC1") (pin "17") (pinfunction "PA9[PA11]_17") (pintype "bidirectional"))
      (node (ref "IC19") (pin "6") (pinfunction "IO2_6") (pintype "bidirectional"))
      (node (ref "R6") (pin "1") (pinfunction "1_1") (pintype "bidirectional"))
    )
    (net (code "63") (name "USB-DP") (class "Default")
      (node (ref "IC1") (pin "18") (pinfunction "PA10[PA12]_18") (pintype "bidirectional"))
      (node (ref "IC19") (pin "1") (pinfunction "IO1_1") (pintype "bidirectional"))
      (node (ref "R20") (pin "2") (pinfunction "2_2") (pintype "bidirectional"))
    )
    (net (code "64") (name "USB_PRES") (class "Default")
      (node (ref "IC1") (pin "14") (pinfunction "PB1_14") (pintype "bidirectional"))
      (node (ref "R16") (pin "2") (pinfunction "2_2") (pintype "bidirectional"))
      (node (ref "R17") (pin "2") (pinfunction "2_2") (pintype "bidirectional"))
      (node (ref "S2") (pin "1") (pinfunction "P_1") (pintype "passive"))
      (node (ref "S2") (pin "2") (pinfunction "P_2") (pintype "passive"))
    )
    (net (code "65") (name "unconnected-(IC1-PA0-Pad6)") (class "Default")
      (node (ref "IC1") (pin "6") (pinfunction "PA0_6") (pintype "bidirectional"))
    )
    (net (code "66") (name "unconnected-(IC1-PA6-Pad12)") (class "Default")
      (node (ref "IC1") (pin "12") (pinfunction "PA6_12") (pintype "bidirectional"))
    )
    (net (code "67") (name "unconnected-(IC17-CKO-Pad5)") (class "Default")
      (node (ref "IC17") (pin "5") (pinfunction "CKO_5") (pintype "bidirectional"))
    )
    (net (code "68") (name "unconnected-(IC17-SDO-Pad6)") (class "Default")
      (node (ref "IC17") (pin "6") (pinfunction "SDO_6") (pintype "bidirectional"))
    )
    (net (code "69") (name "unconnected-(IC18-ONA-Pad7)") (class "Default")
      (node (ref "IC18") (pin "7") (pinfunction "ONA_7") (pintype "bidirectional"))
    )
    (net (code "70") (name "unconnected-(IC19-NC1-Pad3)") (class "Default")
      (node (ref "IC19") (pin "3") (pinfunction "NC1_3") (pintype "bidirectional"))
    )
    (net (code "71") (name "unconnected-(IC19-NC2-Pad4)") (class "Default")
      (node (ref "IC19") (pin "4") (pinfunction "NC2_4") (pintype "bidirectional"))
    )
  )
)
